# motorEncoder.net
KiCad netlist of a schematic drawn in Altium Designer
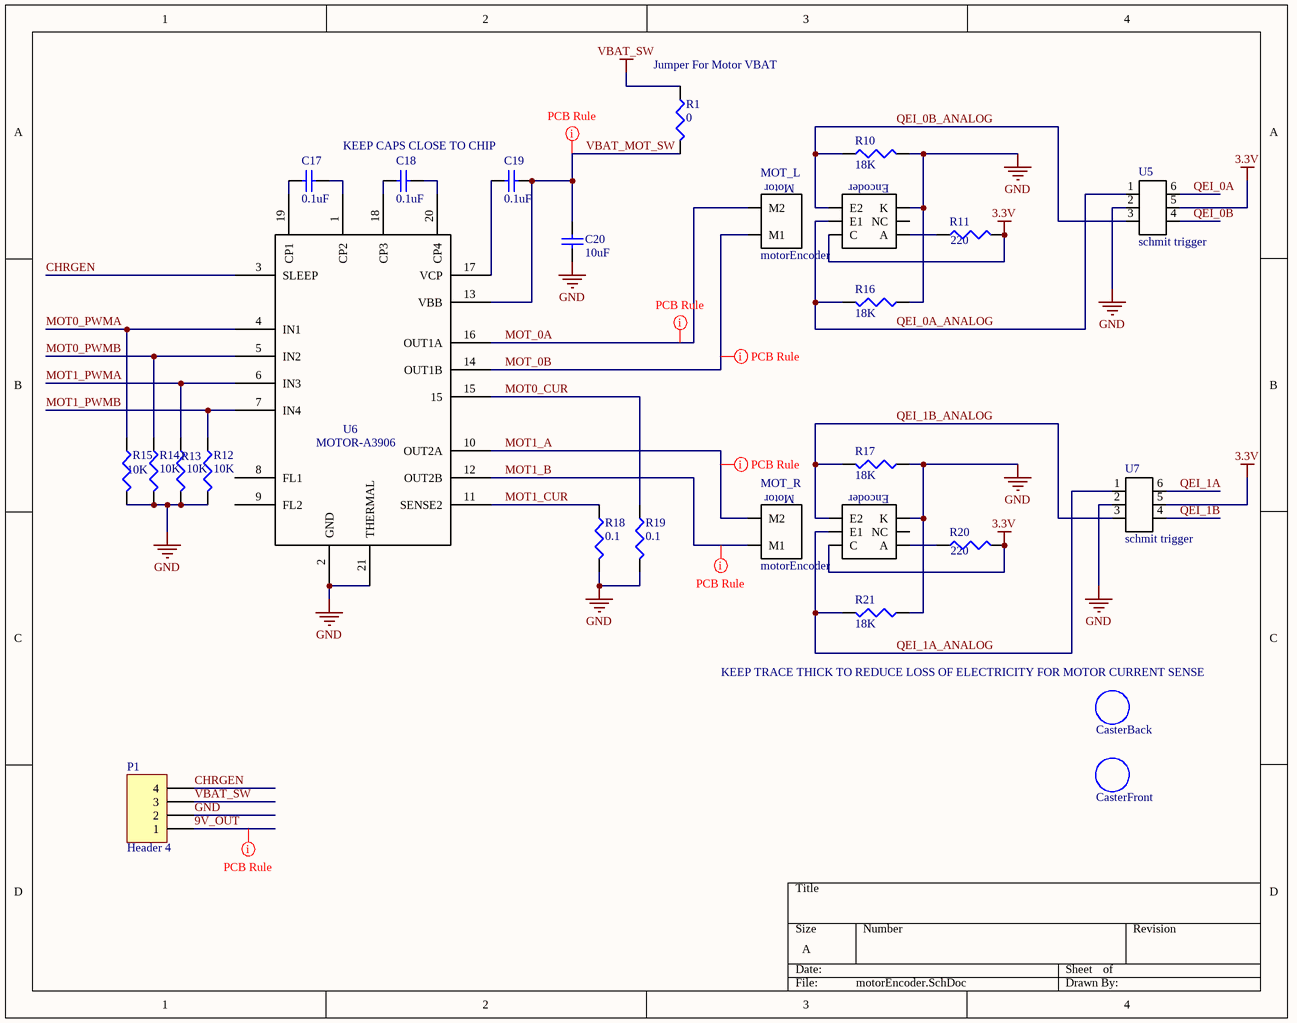
[diagram p0: motorEncoder.SchDoc]

(export (version "E")
  (design (tool "Eeschema 10.0.6"))
  (components
    (comp (ref "C17")
      (value "0.1uF")
      (footprint "CAPC1005L")
      (description "Capacitor (Semiconductor SIM Model)")
      (fields (field (name "Comment") "Cap Semi") (field (name "PUBLISHER") "Altium Limited"))
      (libsource (lib "Miscellaneous Devices") (part "Cap Semi"))
    )
    (comp (ref "C18")
      (value "0.1uF")
      (footprint "CAPC1005L")
      (description "Capacitor (Semiconductor SIM Model)")
      (fields (field (name "Comment") "Cap Semi") (field (name "PUBLISHER") "Altium Limited"))
      (libsource (lib "Miscellaneous Devices") (part "Cap Semi"))
    )
    (comp (ref "C19")
      (value "0.1uF")
      (footprint "CAPC1005L")
      (description "Capacitor (Semiconductor SIM Model)")
      (fields (field (name "Comment") "Cap Semi") (field (name "PUBLISHER") "Altium Limited"))
      (libsource (lib "Miscellaneous Devices") (part "Cap Semi"))
    )
    (comp (ref "C20")
      (value "10uF")
      (footprint "CAPC1608L")
      (description "Capacitor (Semiconductor SIM Model)")
      (fields (field (name "Comment") "Cap Semi") (field (name "PUBLISHER") "Altium Limited"))
      (libsource (lib "Miscellaneous Devices") (part "Cap Semi"))
    )
    (comp (ref "CasterBack")
      (value "non connect")
      (footprint "3/8\"Caster")
      (description "This is just a space saver to get the caster onto the pcb")
      (libsource (lib "mrone") (part "Caster"))
    )
    (comp (ref "CasterFront")
      (value "non connect")
      (footprint "3/8\"Caster")
      (description "This is just a space saver to get the caster onto the pcb")
      (libsource (lib "mrone") (part "Caster"))
    )
    (comp (ref "MOT_L")
      (value "motorEncoder")
      (footprint "motorEncoder")
      (libsource (lib "mrone") (part "motorEncoder"))
    )
    (comp (ref "MOT_R")
      (value "motorEncoder")
      (footprint "motorEncoder")
      (libsource (lib "mrone") (part "motorEncoder"))
    )
    (comp (ref "P1")
      (value "Header 4")
      (footprint "HDR1X4")
      (description "Header, 4-Pin")
      (fields (field (name "PUBLISHER") "Altium Limited"))
      (libsource (lib "Miscellaneous Connectors") (part "Header 4"))
    )
    (comp (ref "R1")
      (value "0")
      (footprint "RESC3225L")
      (description "Resistor")
      (fields (field (name "Comment") "Res3") (field (name "PUBLISHER") "Altium Limited"))
      (libsource (lib "Miscellaneous Devices") (part "Res3"))
    )
    (comp (ref "R10")
      (value "18K")
      (footprint "RESC1608L")
      (description "Resistor")
      (fields (field (name "PUBLISHER") "Altium Limited"))
      (libsource (lib "Miscellaneous Devices") (part "Res3"))
    )
    (comp (ref "R11")
      (value "220")
      (footprint "RESC1608L")
      (description "Resistor")
      (fields (field (name "PUBLISHER") "Altium Limited"))
      (libsource (lib "Miscellaneous Devices") (part "Res3"))
    )
    (comp (ref "R12")
      (value "10K")
      (footprint "RESC1608L")
      (description "Resistor")
      (fields (field (name "Comment") "Res3") (field (name "PUBLISHER") "Altium Limited"))
      (libsource (lib "Miscellaneous Devices") (part "Res3"))
    )
    (comp (ref "R13")
      (value "10K")
      (footprint "RESC1608L")
      (description "Resistor")
      (fields (field (name "Comment") "Res3") (field (name "PUBLISHER") "Altium Limited"))
      (libsource (lib "Miscellaneous Devices") (part "Res3"))
    )
    (comp (ref "R14")
      (value "10K")
      (footprint "RESC1608L")
      (description "Resistor")
      (fields (field (name "Comment") "Res3") (field (name "PUBLISHER") "Altium Limited"))
      (libsource (lib "Miscellaneous Devices") (part "Res3"))
    )
    (comp (ref "R15")
      (value "10K")
      (footprint "RESC1608L")
      (description "Resistor")
      (fields (field (name "Comment") "Res3") (field (name "PUBLISHER") "Altium Limited"))
      (libsource (lib "Miscellaneous Devices") (part "Res3"))
    )
    (comp (ref "R16")
      (value "18K")
      (footprint "RESC1608L")
      (description "Resistor")
      (fields (field (name "PUBLISHER") "Altium Limited"))
      (libsource (lib "Miscellaneous Devices") (part "Res3"))
    )
    (comp (ref "R17")
      (value "18K")
      (footprint "RESC1608L")
      (description "Resistor")
      (fields (field (name "PUBLISHER") "Altium Limited"))
      (libsource (lib "Miscellaneous Devices") (part "Res3"))
    )
    (comp (ref "R18")
      (value "0.1")
      (footprint "RESC1608L")
      (description "Resistor")
      (fields (field (name "Comment") "Res3") (field (name "PUBLISHER") "Altium Limited"))
      (libsource (lib "Miscellaneous Devices") (part "Res3"))
    )
    (comp (ref "R19")
      (value "0.1")
      (footprint "RESC1608L")
      (description "Resistor")
      (fields (field (name "Comment") "Res3") (field (name "PUBLISHER") "Altium Limited"))
      (libsource (lib "Miscellaneous Devices") (part "Res3"))
    )
    (comp (ref "R20")
      (value "220")
      (footprint "RESC1608L")
      (description "Resistor")
      (fields (field (name "PUBLISHER") "Altium Limited"))
      (libsource (lib "Miscellaneous Devices") (part "Res3"))
    )
    (comp (ref "R21")
      (value "18K")
      (footprint "RESC1608L")
      (description "Resistor")
      (fields (field (name "PUBLISHER") "Altium Limited"))
      (libsource (lib "Miscellaneous Devices") (part "Res3"))
    )
    (comp (ref "U5")
      (value "schmit trigger")
      (footprint "DCK(R-PDSO-C6)")
      (libsource (lib "mrone") (part "schmit trigger"))
    )
    (comp (ref "U6")
      (value "MOTOR-A3906")
      (footprint "QFN-20")
      (libsource (lib "V2_altium") (part "MOTOR-A3906"))
    )
    (comp (ref "U7")
      (value "schmit trigger")
      (footprint "DCK(R-PDSO-C6)")
      (libsource (lib "mrone") (part "schmit trigger"))
    )
  )
  (nets
    (net (code "1") (name "/9V_OUT") (class "Default")
      (node (ref "P1") (pin "1") (pinfunction "1_1") (pintype "passive"))
    )
    (net (code "3") (name "/CHRGEN") (class "Default")
      (node (ref "P1") (pin "4") (pinfunction "4_4") (pintype "passive"))
      (node (ref "U6") (pin "3") (pinfunction "SLEEP_3") (pintype "passive"))
    )
    (net (code "4") (name "/MOT0_CUR") (class "Default")
      (node (ref "R19") (pin "1") (pinfunction "1_1") (pintype "passive"))
      (node (ref "U6") (pin "15") (pinfunction "15_15") (pintype "passive"))
    )
    (net (code "5") (name "/MOT0_PWMA") (class "Default")
      (node (ref "R15") (pin "1") (pinfunction "1_1") (pintype "passive"))
      (node (ref "U6") (pin "4") (pinfunction "IN1_4") (pintype "passive"))
    )
    (net (code "6") (name "/MOT0_PWMB") (class "Default")
      (node (ref "R14") (pin "1") (pinfunction "1_1") (pintype "passive"))
      (node (ref "U6") (pin "5") (pinfunction "IN2_5") (pintype "passive"))
    )
    (net (code "7") (name "/MOT1_A") (class "Default")
      (node (ref "MOT_R") (pin "M2") (pinfunction "M2_M2") (pintype "passive"))
      (node (ref "U6") (pin "10") (pinfunction "OUT2A_10") (pintype "passive"))
    )
    (net (code "8") (name "/MOT1_B") (class "Default")
      (node (ref "MOT_R") (pin "M1") (pinfunction "M1_M1") (pintype "passive"))
      (node (ref "U6") (pin "12") (pinfunction "OUT2B_12") (pintype "passive"))
    )
    (net (code "9") (name "/MOT1_CUR") (class "Default")
      (node (ref "R18") (pin "1") (pinfunction "1_1") (pintype "passive"))
      (node (ref "U6") (pin "11") (pinfunction "SENSE2_11") (pintype "passive"))
    )
    (net (code "10") (name "/MOT1_PWMA") (class "Default")
      (node (ref "R13") (pin "1") (pinfunction "1_1") (pintype "passive"))
      (node (ref "U6") (pin "6") (pinfunction "IN3_6") (pintype "passive"))
    )
    (net (code "11") (name "/MOT1_PWMB") (class "Default")
      (node (ref "R12") (pin "1") (pinfunction "1_1") (pintype "passive"))
      (node (ref "U6") (pin "7") (pinfunction "IN4_7") (pintype "passive"))
    )
    (net (code "12") (name "/MOT_0A") (class "Default")
      (node (ref "MOT_L") (pin "M2") (pinfunction "M2_M2") (pintype "passive"))
      (node (ref "U6") (pin "16") (pinfunction "OUT1A_16") (pintype "passive"))
    )
    (net (code "13") (name "/MOT_0B") (class "Default")
      (node (ref "MOT_L") (pin "M1") (pinfunction "M1_M1") (pintype "passive"))
      (node (ref "U6") (pin "14") (pinfunction "OUT1B_14") (pintype "passive"))
    )
    (net (code "14") (name "/QEI_0A") (class "Default")
      (node (ref "U5") (pin "6") (pinfunction "4_6") (pintype "passive"))
    )
    (net (code "15") (name "/QEI_0A_ANALOG") (class "Default")
      (node (ref "MOT_L") (pin "E1") (pinfunction "E1_E1") (pintype "passive"))
      (node (ref "R16") (pin "2") (pinfunction "2_2") (pintype "passive"))
      (node (ref "U5") (pin "1") (pinfunction "1_1") (pintype "passive"))
    )
    (net (code "16") (name "/QEI_0B") (class "Default")
      (node (ref "U5") (pin "4") (pinfunction "4_4") (pintype "passive"))
    )
    (net (code "17") (name "/QEI_0B_ANALOG") (class "Default")
      (node (ref "MOT_L") (pin "E2") (pinfunction "E2_E2") (pintype "passive"))
      (node (ref "R10") (pin "1") (pinfunction "1_1") (pintype "passive"))
      (node (ref "U5") (pin "3") (pinfunction "3_3") (pintype "passive"))
    )
    (net (code "18") (name "/QEI_1A") (class "Default")
      (node (ref "U7") (pin "6") (pinfunction "4_6") (pintype "passive"))
    )
    (net (code "19") (name "/QEI_1A_ANALOG") (class "Default")
      (node (ref "MOT_R") (pin "E1") (pinfunction "E1_E1") (pintype "passive"))
      (node (ref "R21") (pin "2") (pinfunction "2_2") (pintype "passive"))
      (node (ref "U7") (pin "1") (pinfunction "1_1") (pintype "passive"))
    )
    (net (code "20") (name "/QEI_1B") (class "Default")
      (node (ref "U7") (pin "4") (pinfunction "4_4") (pintype "passive"))
    )
    (net (code "21") (name "/QEI_1B_ANALOG") (class "Default")
      (node (ref "MOT_R") (pin "E2") (pinfunction "E2_E2") (pintype "passive"))
      (node (ref "R17") (pin "2") (pinfunction "2_2") (pintype "passive"))
      (node (ref "U7") (pin "3") (pinfunction "3_3") (pintype "passive"))
    )
    (net (code "22") (name "/VBAT_MOT_SW") (class "Default")
      (node (ref "C19") (pin "1") (pinfunction "1_1") (pintype "passive"))
      (node (ref "C20") (pin "2") (pinfunction "2_2") (pintype "passive"))
      (node (ref "R1") (pin "2") (pinfunction "2_2") (pintype "passive"))
      (node (ref "U6") (pin "13") (pinfunction "VBB_13") (pintype "passive"))
    )
    (net (code "23") (name "3.3V") (class "Default")
      (node (ref "MOT_L") (pin "C") (pinfunction "C_C") (pintype "passive"))
      (node (ref "MOT_R") (pin "C") (pinfunction "C_C") (pintype "passive"))
      (node (ref "R11") (pin "2") (pinfunction "2_2") (pintype "passive"))
      (node (ref "R20") (pin "2") (pinfunction "2_2") (pintype "passive"))
      (node (ref "U5") (pin "5") (pinfunction "5_5") (pintype "passive"))
      (node (ref "U7") (pin "5") (pinfunction "5_5") (pintype "passive"))
    )
    (net (code "24") (name "GND") (class "Default")
      (node (ref "C20") (pin "1") (pinfunction "1_1") (pintype "passive"))
      (node (ref "MOT_L") (pin "K") (pinfunction "K_K") (pintype "passive"))
      (node (ref "MOT_R") (pin "K") (pinfunction "K_K") (pintype "passive"))
      (node (ref "P1") (pin "2") (pinfunction "2_2") (pintype "passive"))
      (node (ref "R10") (pin "2") (pinfunction "2_2") (pintype "passive"))
      (node (ref "R12") (pin "2") (pinfunction "2_2") (pintype "passive"))
      (node (ref "R13") (pin "2") (pinfunction "2_2") (pintype "passive"))
      (node (ref "R14") (pin "2") (pinfunction "2_2") (pintype "passive"))
      (node (ref "R15") (pin "2") (pinfunction "2_2") (pintype "passive"))
      (node (ref "R16") (pin "1") (pinfunction "1_1") (pintype "passive"))
      (node (ref "R17") (pin "1") (pinfunction "1_1") (pintype "passive"))
      (node (ref "R18") (pin "2") (pinfunction "2_2") (pintype "passive"))
      (node (ref "R19") (pin "2") (pinfunction "2_2") (pintype "passive"))
      (node (ref "R21") (pin "1") (pinfunction "1_1") (pintype "passive"))
      (node (ref "U5") (pin "2") (pinfunction "2_2") (pintype "passive"))
      (node (ref "U6") (pin "2") (pinfunction "GND_2") (pintype "passive"))
      (node (ref "U6") (pin "21") (pinfunction "THERMAL_21") (pintype "passive"))
      (node (ref "U7") (pin "2") (pinfunction "2_2") (pintype "passive"))
    )
    (net (code "25") (name "Net-(MOT_L-PadA)") (class "Default")
      (node (ref "MOT_L") (pin "A") (pinfunction "A_A") (pintype "passive"))
      (node (ref "R11") (pin "1") (pinfunction "1_1") (pintype "passive"))
    )
    (net (code "26") (name "Net-(MOT_R-PadA)") (class "Default")
      (node (ref "MOT_R") (pin "A") (pinfunction "A_A") (pintype "passive"))
      (node (ref "R20") (pin "1") (pinfunction "1_1") (pintype "passive"))
    )
    (net (code "27") (name "Net-(U6-CP1)") (class "Default")
      (node (ref "C17") (pin "1") (pinfunction "1_1") (pintype "passive"))
      (node (ref "U6") (pin "19") (pinfunction "CP1_19") (pintype "passive"))
    )
    (net (code "28") (name "Net-(U6-CP2)") (class "Default")
      (node (ref "C17") (pin "2") (pinfunction "2_2") (pintype "passive"))
      (node (ref "U6") (pin "1") (pinfunction "CP2_1") (pintype "passive"))
    )
    (net (code "29") (name "Net-(U6-CP3)") (class "Default")
      (node (ref "C18") (pin "1") (pinfunction "1_1") (pintype "passive"))
      (node (ref "U6") (pin "18") (pinfunction "CP3_18") (pintype "passive"))
    )
    (net (code "30") (name "Net-(U6-CP4)") (class "Default")
      (node (ref "C18") (pin "2") (pinfunction "2_2") (pintype "passive"))
      (node (ref "U6") (pin "20") (pinfunction "CP4_20") (pintype "passive"))
    )
    (net (code "31") (name "Net-(U6-VCP)") (class "Default")
      (node (ref "C19") (pin "2") (pinfunction "2_2") (pintype "passive"))
      (node (ref "U6") (pin "17") (pinfunction "VCP_17") (pintype "passive"))
    )
    (net (code "32") (name "VBAT_SW") (class "Default")
      (node (ref "P1") (pin "3") (pinfunction "3_3") (pintype "passive"))
      (node (ref "R1") (pin "1") (pinfunction "1_1") (pintype "passive"))
    )
    (net (code "33") (name "unconnected-(MOT_L-PadNC)") (class "Default")
      (node (ref "MOT_L") (pin "NC") (pinfunction "NC_NC") (pintype "passive"))
    )
    (net (code "34") (name "unconnected-(MOT_R-PadNC)") (class "Default")
      (node (ref "MOT_R") (pin "NC") (pinfunction "NC_NC") (pintype "passive"))
    )
    (net (code "35") (name "unconnected-(U6-FL1-Pad8)") (class "Default")
      (node (ref "U6") (pin "8") (pinfunction "FL1_8") (pintype "passive"))
    )
    (net (code "36") (name "unconnected-(U6-FL2-Pad9)") (class "Default")
      (node (ref "U6") (pin "9") (pinfunction "FL2_9") (pintype "passive"))
    )
  )
)
